# Soprano2G-171.net
KiCad netlist of a schematic drawn in EAGLE
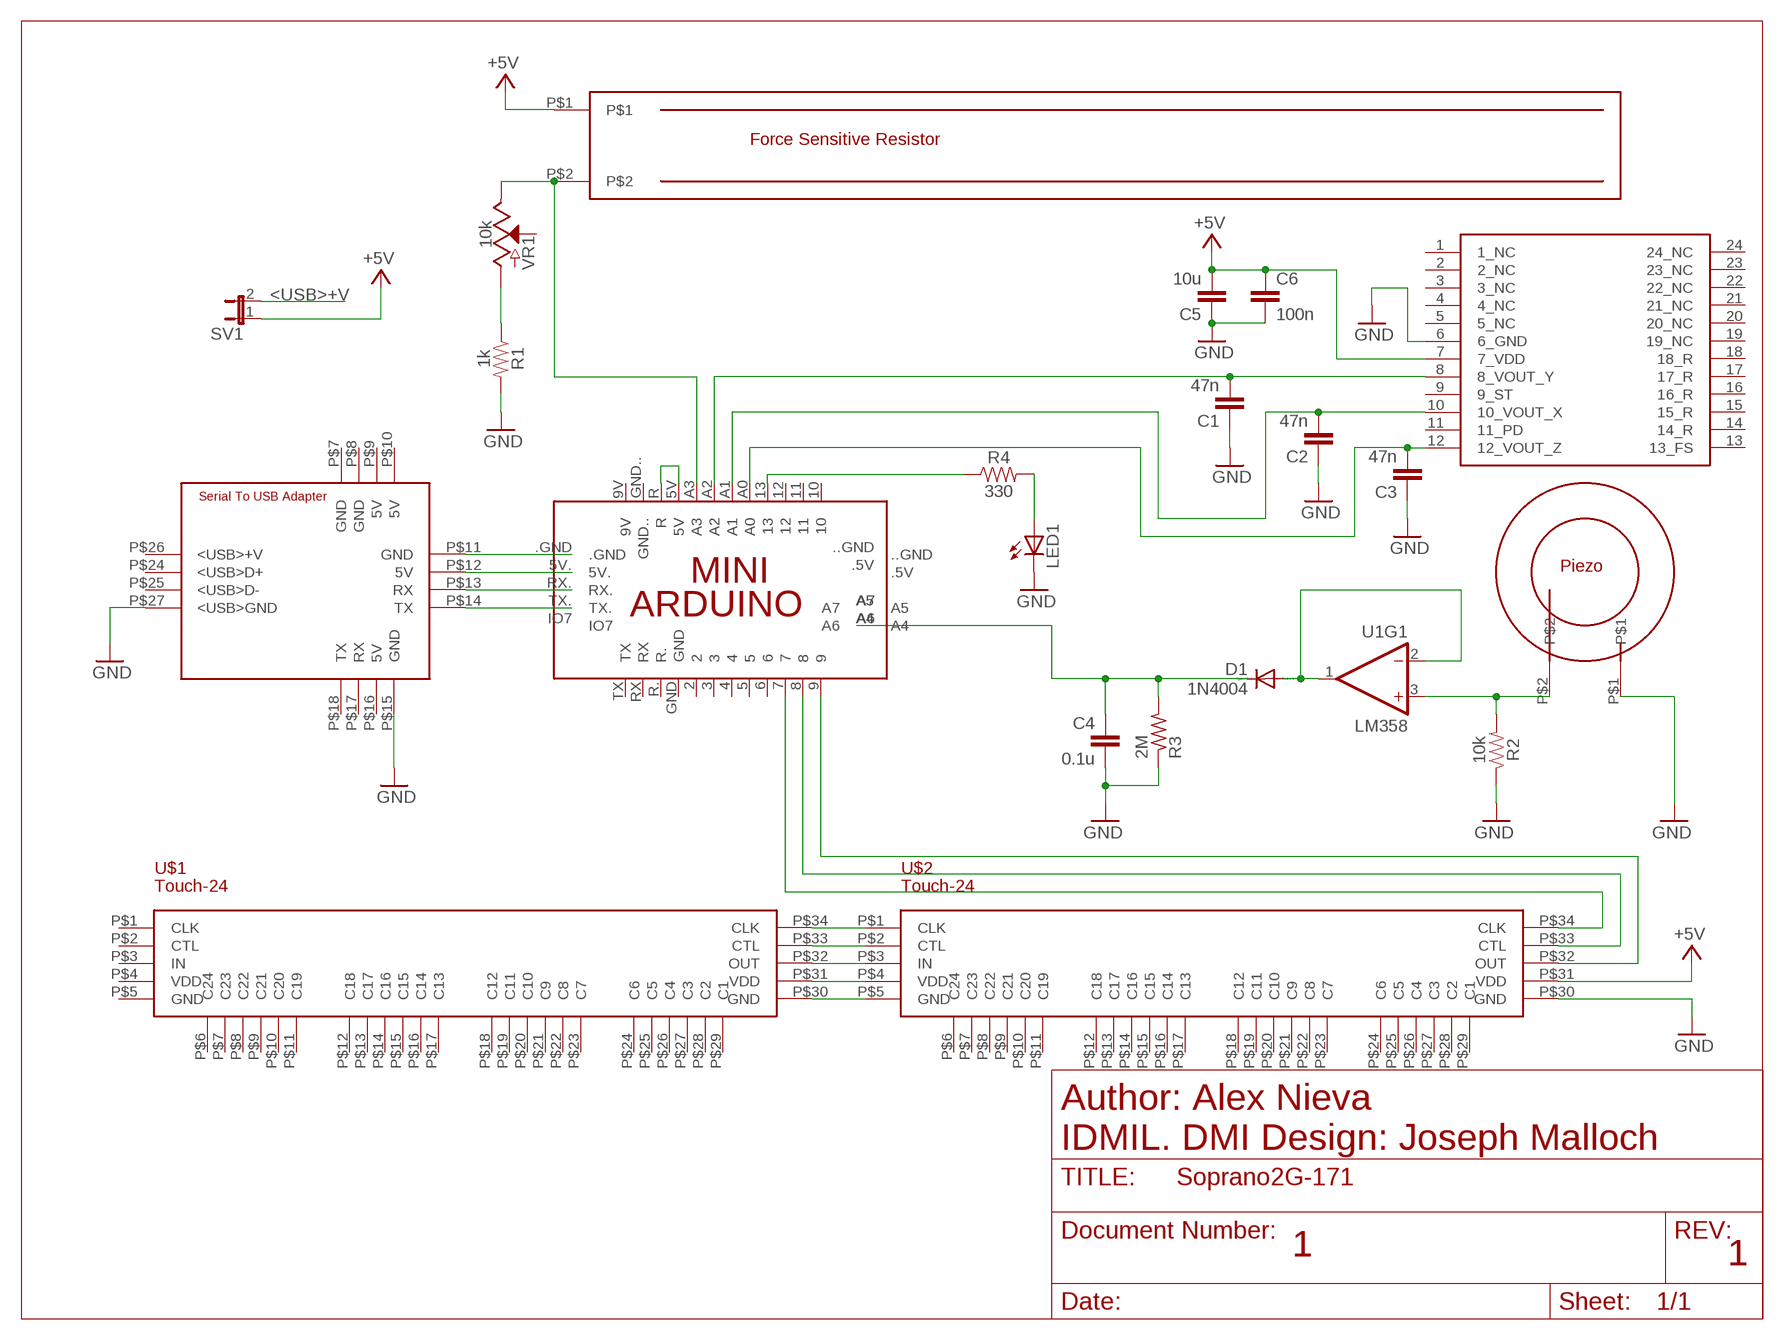
[diagram p0: schematic, sheet 1]

(export (version "E")
  (design (tool "Eeschema 10.0.6"))
  (components
    (comp (ref "C1")
      (value "47n")
      (footprint "eagle-import:C5B5.5")
      (libsource (lib "eagle-import") (part "C5/5.5"))
    )
    (comp (ref "C2")
      (value "47n")
      (footprint "eagle-import:C5B5.5")
      (libsource (lib "eagle-import") (part "C5/5.5"))
    )
    (comp (ref "C3")
      (value "47n")
      (footprint "eagle-import:C5B5.5")
      (libsource (lib "eagle-import") (part "C5/5.5"))
    )
    (comp (ref "C4")
      (value "0.1u")
      (footprint "eagle-import:C5B5.5")
      (libsource (lib "eagle-import") (part "C5/5.5"))
    )
    (comp (ref "C5")
      (value "10u")
      (footprint "eagle-import:C5B5.5")
      (libsource (lib "eagle-import") (part "C5/5.5"))
    )
    (comp (ref "C6")
      (value "100n")
      (footprint "eagle-import:C5B5.5")
      (libsource (lib "eagle-import") (part "C5/5.5"))
    )
    (comp (ref "D1")
      (value "1N4004")
      (footprint "eagle-import:DO41-10")
      (libsource (lib "eagle-import") (part "1N4004"))
    )
    (comp (ref "LED1")
      (value "LED3MM")
      (footprint "eagle-import:LED3MM")
      (libsource (lib "eagle-import") (part "LED3MM"))
    )
    (comp (ref "PCB1")
      (value "ARDUINO_MINI")
      (footprint "eagle-import:ARDUINO_MINI")
      (libsource (lib "eagle-import") (part "ARDUINO_MINI"))
    )
    (comp (ref "R1")
      (value "1k")
      (footprint "eagle-import:AXIAL-0.3")
      (libsource (lib "eagle-import") (part "1KOHM-HORIZ-1/4W-1%"))
    )
    (comp (ref "R2")
      (value "10k")
      (footprint "eagle-import:AXIAL-0.3")
      (libsource (lib "eagle-import") (part "10KOHM-HORIZ-1/4W-1%"))
    )
    (comp (ref "R3")
      (value "2M")
      (footprint "eagle-import:0204_7")
      (libsource (lib "eagle-import") (part "R-US_0204/7"))
    )
    (comp (ref "R4")
      (value "330")
      (footprint "eagle-import:AXIAL-0.3")
      (libsource (lib "eagle-import") (part "1KOHM-HORIZ-1/4W-1%"))
    )
    (comp (ref "SV1")
      (value "JP1E")
      (footprint "eagle-import:JP1")
      (libsource (lib "eagle-import") (part "JP1E"))
    )
    (comp (ref "U$1")
      (value "TOUCH-24TOUCH-24")
      (footprint "eagle-import:TOUCH24")
      (libsource (lib "eagle-import") (part "TOUCH-24TOUCH-24"))
    )
    (comp (ref "U$2")
      (value "TOUCH-24TOUCH-24")
      (footprint "eagle-import:TOUCH24")
      (libsource (lib "eagle-import") (part "TOUCH-24TOUCH-24"))
    )
    (comp (ref "U$3")
      (value "LIS3L02AS4")
      (footprint "eagle-import:SO-24")
      (libsource (lib "eagle-import") (part "LIS3L02AS4"))
    )
    (comp (ref "U$4")
      (value "SERIAL_TO_USB_ARDUINO_MINI")
      (footprint "eagle-import:SERIAL_TO_USB_ARDUINO")
      (libsource (lib "eagle-import") (part "SERIAL_TO_USB_ARDUINO_MINI"))
    )
    (comp (ref "U$5")
      (value "FSR_T-STICK")
      (footprint "eagle-import:FSR_T-STICK")
      (libsource (lib "eagle-import") (part "FSR_T-STICK"))
    )
    (comp (ref "U$6")
      (value "PIEZO_TSTICK")
      (footprint "eagle-import:PIEZO_TSTICK")
      (libsource (lib "eagle-import") (part "PIEZO_TSTICK"))
    )
    (comp (ref "U1")
      (value "LM358")
      (footprint "eagle-import:DIP08")
      (libsource (lib "eagle-import") (part "LM358"))
    )
    (comp (ref "VR1")
      (value "10k")
      (footprint "eagle-import:POT-PTH-ALPS")
      (libsource (lib "eagle-import") (part "POTENTIOMETER-PTH-9MM-1/20W-20%"))
    )
  )
  (nets
    (net (code "1") (name "+5V") (class "Default")
      (node (ref "C5") (pin "2") (pinfunction "2_2") (pintype "passive"))
      (node (ref "C6") (pin "1") (pinfunction "1_1") (pintype "passive"))
      (node (ref "PCB1") (pin "5V.") (pinfunction "5V._5V.") (pintype "bidirectional"))
      (node (ref "SV1") (pin "1") (pinfunction "1_1") (pintype "passive"))
      (node (ref "U$2") (pin "P$31") (pinfunction "VDD_P$31") (pintype "bidirectional"))
      (node (ref "U$3") (pin "7") (pinfunction "7_VDD_7") (pintype "bidirectional"))
      (node (ref "U$4") (pin "P$12") (pinfunction "5V_P$12") (pintype "bidirectional"))
      (node (ref "U$5") (pin "P$1") (pinfunction "P$1_P$1") (pintype "bidirectional"))
    )
    (net (code "2") (name "/<USB>+V") (class "Default")
      (node (ref "SV1") (pin "2") (pinfunction "2_2") (pintype "passive"))
    )
    (net (code "3") (name "GND") (class "Default")
      (node (ref "C1") (pin "1") (pinfunction "1_1") (pintype "passive"))
      (node (ref "C2") (pin "1") (pinfunction "1_1") (pintype "passive"))
      (node (ref "C3") (pin "1") (pinfunction "1_1") (pintype "passive"))
      (node (ref "C4") (pin "2") (pinfunction "2_2") (pintype "passive"))
      (node (ref "C5") (pin "1") (pinfunction "1_1") (pintype "passive"))
      (node (ref "C6") (pin "2") (pinfunction "2_2") (pintype "passive"))
      (node (ref "LED1") (pin "K") (pinfunction "C_K") (pintype "passive"))
      (node (ref "R1") (pin "P$2") (pinfunction "2_P$2") (pintype "passive"))
      (node (ref "R2") (pin "P$1") (pinfunction "1_P$1") (pintype "passive"))
      (node (ref "R3") (pin "1") (pinfunction "1_1") (pintype "passive"))
      (node (ref "U$2") (pin "P$30") (pinfunction "GND_P$30") (pintype "bidirectional"))
      (node (ref "U$3") (pin "6") (pinfunction "6_GND_6") (pintype "bidirectional"))
      (node (ref "U$4") (pin "P$15") (pinfunction "GND_P$15") (pintype "bidirectional"))
      (node (ref "U$4") (pin "P$27") (pinfunction "<USB>GND_P$27") (pintype "bidirectional"))
      (node (ref "U$6") (pin "P$1") (pinfunction "P$1_P$1") (pintype "bidirectional"))
    )
    (net (code "4") (name "Net-(C4-Pad1)") (class "Default")
      (node (ref "C4") (pin "1") (pinfunction "1_1") (pintype "passive"))
      (node (ref "D1") (pin "C") (pinfunction "C_C") (pintype "passive"))
      (node (ref "PCB1") (pin "A6") (pinfunction "A6_A6") (pintype "bidirectional"))
      (node (ref "R3") (pin "2") (pinfunction "2_2") (pintype "passive"))
    )
    (net (code "5") (name "Net-(PCB1-Pad.GND)") (class "Default")
      (node (ref "PCB1") (pin ".GND") (pinfunction ".GND_.GND") (pintype "bidirectional"))
      (node (ref "U$4") (pin "P$11") (pinfunction "GND_P$11") (pintype "bidirectional"))
    )
    (net (code "6") (name "Net-(PCB1-Pad5V)") (class "Default")
      (node (ref "PCB1") (pin "5V") (pinfunction "5V_5V") (pintype "bidirectional"))
      (node (ref "PCB1") (pin "R") (pinfunction "R_R") (pintype "bidirectional"))
    )
    (net (code "7") (name "Net-(PCB1-Pad7)") (class "Default")
      (node (ref "PCB1") (pin "7") (pinfunction "7_7") (pintype "bidirectional"))
      (node (ref "U$2") (pin "P$34") (pinfunction "CLK_P$34") (pintype "bidirectional"))
    )
    (net (code "8") (name "Net-(PCB1-Pad8)") (class "Default")
      (node (ref "PCB1") (pin "8") (pinfunction "8_8") (pintype "bidirectional"))
      (node (ref "U$2") (pin "P$33") (pinfunction "CTL_P$33") (pintype "bidirectional"))
    )
    (net (code "9") (name "Net-(PCB1-PadRX.)") (class "Default")
      (node (ref "PCB1") (pin "RX.") (pinfunction "RX._RX.") (pintype "bidirectional"))
      (node (ref "U$4") (pin "P$13") (pinfunction "RX_P$13") (pintype "bidirectional"))
    )
    (net (code "10") (name "Net-(PCB1-PadTX.)") (class "Default")
      (node (ref "PCB1") (pin "TX.") (pinfunction "TX._TX.") (pintype "bidirectional"))
      (node (ref "U$4") (pin "P$14") (pinfunction "TX_P$14") (pintype "bidirectional"))
    )
    (net (code "11") (name "Net-(R1-1)") (class "Default")
      (node (ref "R1") (pin "P$1") (pinfunction "1_P$1") (pintype "passive"))
      (node (ref "VR1") (pin "P$3") (pinfunction "A_P$3") (pintype "passive"))
    )
    (net (code "12") (name "Net-(R2-2)") (class "Default")
      (node (ref "R2") (pin "P$2") (pinfunction "2_P$2") (pintype "passive"))
      (node (ref "U$6") (pin "P$2") (pinfunction "P$2_P$2") (pintype "bidirectional"))
      (node (ref "U1") (pin "3") (pinfunction "+IN_3") (pintype "input"))
    )
    (net (code "13") (name "Net-(R4-1)") (class "Default")
      (node (ref "PCB1") (pin "13") (pinfunction "13_13") (pintype "bidirectional"))
      (node (ref "R4") (pin "P$1") (pinfunction "1_P$1") (pintype "passive"))
    )
    (net (code "14") (name "Net-(R4-2)") (class "Default")
      (node (ref "LED1") (pin "A") (pinfunction "A_A") (pintype "passive"))
      (node (ref "R4") (pin "P$2") (pinfunction "2_P$2") (pintype "passive"))
    )
    (net (code "15") (name "Net-(U$1-CLK-PadP$34)") (class "Default")
      (node (ref "U$1") (pin "P$34") (pinfunction "CLK_P$34") (pintype "bidirectional"))
      (node (ref "U$2") (pin "P$1") (pinfunction "CLK_P$1") (pintype "bidirectional"))
    )
    (net (code "16") (name "Net-(U$1-CTL-PadP$33)") (class "Default")
      (node (ref "U$1") (pin "P$33") (pinfunction "CTL_P$33") (pintype "bidirectional"))
      (node (ref "U$2") (pin "P$2") (pinfunction "CTL_P$2") (pintype "bidirectional"))
    )
    (net (code "17") (name "Net-(U$1-GND-PadP$30)") (class "Default")
      (node (ref "U$1") (pin "P$30") (pinfunction "GND_P$30") (pintype "bidirectional"))
      (node (ref "U$2") (pin "P$5") (pinfunction "GND_P$5") (pintype "bidirectional"))
    )
    (net (code "18") (name "Net-(U$1-OUT)") (class "Default")
      (node (ref "U$1") (pin "P$32") (pinfunction "OUT_P$32") (pintype "bidirectional"))
      (node (ref "U$2") (pin "P$3") (pinfunction "IN_P$3") (pintype "bidirectional"))
    )
    (net (code "19") (name "Net-(U$1-VDD-PadP$31)") (class "Default")
      (node (ref "U$1") (pin "P$31") (pinfunction "VDD_P$31") (pintype "bidirectional"))
      (node (ref "U$2") (pin "P$4") (pinfunction "VDD_P$4") (pintype "bidirectional"))
    )
    (net (code "20") (name "Net-(U$2-OUT)") (class "Default")
      (node (ref "PCB1") (pin "9") (pinfunction "9_9") (pintype "bidirectional"))
      (node (ref "U$2") (pin "P$32") (pinfunction "OUT_P$32") (pintype "bidirectional"))
    )
    (net (code "21") (name "Net-(U$3-8_VOUT_Y)") (class "Default")
      (node (ref "C1") (pin "2") (pinfunction "2_2") (pintype "passive"))
      (node (ref "PCB1") (pin "A2") (pinfunction "A2_A2") (pintype "bidirectional"))
      (node (ref "U$3") (pin "8") (pinfunction "8_VOUT_Y_8") (pintype "bidirectional"))
    )
    (net (code "22") (name "Net-(U$3-10_VOUT_X)") (class "Default")
      (node (ref "C2") (pin "2") (pinfunction "2_2") (pintype "passive"))
      (node (ref "PCB1") (pin "A1") (pinfunction "A1_A1") (pintype "bidirectional"))
      (node (ref "U$3") (pin "10") (pinfunction "10_VOUT_X_10") (pintype "bidirectional"))
    )
    (net (code "23") (name "Net-(U$3-12_VOUT_Z)") (class "Default")
      (node (ref "C3") (pin "2") (pinfunction "2_2") (pintype "passive"))
      (node (ref "PCB1") (pin "A0") (pinfunction "A0_A0") (pintype "bidirectional"))
      (node (ref "U$3") (pin "12") (pinfunction "12_VOUT_Z_12") (pintype "bidirectional"))
    )
    (net (code "24") (name "Net-(U1A--IN)") (class "Default")
      (node (ref "D1") (pin "A") (pinfunction "A_A") (pintype "passive"))
      (node (ref "U1") (pin "1") (pinfunction "OUT_1") (pintype "output"))
      (node (ref "U1") (pin "2") (pinfunction "-IN_2") (pintype "input"))
    )
    (net (code "25") (name "Net-(VR1-E)") (class "Default")
      (node (ref "PCB1") (pin "A3") (pinfunction "A3_A3") (pintype "bidirectional"))
      (node (ref "U$5") (pin "P$2") (pinfunction "P$2_P$2") (pintype "bidirectional"))
      (node (ref "VR1") (pin "P$1") (pinfunction "E_P$1") (pintype "passive"))
    )
    (net (code "26") (name "unconnected-(PCB1-Pad..GND)") (class "Default")
      (node (ref "PCB1") (pin "..GND") (pinfunction "..GND_..GND") (pintype "bidirectional"))
    )
    (net (code "27") (name "unconnected-(PCB1-Pad.5V)") (class "Default")
      (node (ref "PCB1") (pin ".5V") (pinfunction ".5V_.5V") (pintype "bidirectional"))
    )
    (net (code "28") (name "unconnected-(PCB1-Pad2)") (class "Default")
      (node (ref "PCB1") (pin "2") (pinfunction "2_2") (pintype "bidirectional"))
    )
    (net (code "29") (name "unconnected-(PCB1-Pad3)") (class "Default")
      (node (ref "PCB1") (pin "3") (pinfunction "3_3") (pintype "bidirectional"))
    )
    (net (code "30") (name "unconnected-(PCB1-Pad4)") (class "Default")
      (node (ref "PCB1") (pin "4") (pinfunction "4_4") (pintype "bidirectional"))
    )
    (net (code "31") (name "unconnected-(PCB1-Pad5)") (class "Default")
      (node (ref "PCB1") (pin "5") (pinfunction "5_5") (pintype "bidirectional"))
    )
    (net (code "32") (name "unconnected-(PCB1-Pad6)") (class "Default")
      (node (ref "PCB1") (pin "6") (pinfunction "6_6") (pintype "bidirectional"))
    )
    (net (code "33") (name "unconnected-(PCB1-Pad9V)") (class "Default")
      (node (ref "PCB1") (pin "9V") (pinfunction "9V_9V") (pintype "bidirectional"))
    )
    (net (code "34") (name "unconnected-(PCB1-Pad10)") (class "Default")
      (node (ref "PCB1") (pin "10") (pinfunction "10_10") (pintype "bidirectional"))
    )
    (net (code "35") (name "unconnected-(PCB1-Pad11)") (class "Default")
      (node (ref "PCB1") (pin "11") (pinfunction "11_11") (pintype "bidirectional"))
    )
    (net (code "36") (name "unconnected-(PCB1-Pad12)") (class "Default")
      (node (ref "PCB1") (pin "12") (pinfunction "12_12") (pintype "bidirectional"))
    )
    (net (code "37") (name "unconnected-(PCB1-PadA4)") (class "Default")
      (node (ref "PCB1") (pin "A4") (pinfunction "A4_A4") (pintype "bidirectional"))
    )
    (net (code "38") (name "unconnected-(PCB1-PadA5)") (class "Default")
      (node (ref "PCB1") (pin "A5") (pinfunction "A5_A5") (pintype "bidirectional"))
    )
    (net (code "39") (name "unconnected-(PCB1-PadA7)") (class "Default")
      (node (ref "PCB1") (pin "A7") (pinfunction "A7_A7") (pintype "bidirectional"))
    )
    (net (code "40") (name "unconnected-(PCB1-PadGND)") (class "Default")
      (node (ref "PCB1") (pin "GND") (pinfunction "GND_GND") (pintype "bidirectional"))
    )
    (net (code "41") (name "unconnected-(PCB1-PadGND..)") (class "Default")
      (node (ref "PCB1") (pin "GND..") (pinfunction "GND.._GND..") (pintype "bidirectional"))
    )
    (net (code "42") (name "unconnected-(PCB1-PadIO7)") (class "Default")
      (node (ref "PCB1") (pin "IO7") (pinfunction "IO7_IO7") (pintype "bidirectional"))
    )
    (net (code "43") (name "unconnected-(PCB1-PadR.)") (class "Default")
      (node (ref "PCB1") (pin "R.") (pinfunction "R._R.") (pintype "bidirectional"))
    )
    (net (code "44") (name "unconnected-(PCB1-PadRX)") (class "Default")
      (node (ref "PCB1") (pin "RX") (pinfunction "RX_RX") (pintype "bidirectional"))
    )
    (net (code "45") (name "unconnected-(PCB1-PadTX)") (class "Default")
      (node (ref "PCB1") (pin "TX") (pinfunction "TX_TX") (pintype "bidirectional"))
    )
    (net (code "46") (name "unconnected-(U$1-C1-PadP$29)") (class "Default")
      (node (ref "U$1") (pin "P$29") (pinfunction "C1_P$29") (pintype "bidirectional"))
    )
    (net (code "47") (name "unconnected-(U$1-C2-PadP$28)") (class "Default")
      (node (ref "U$1") (pin "P$28") (pinfunction "C2_P$28") (pintype "bidirectional"))
    )
    (net (code "48") (name "unconnected-(U$1-C3-PadP$27)") (class "Default")
      (node (ref "U$1") (pin "P$27") (pinfunction "C3_P$27") (pintype "bidirectional"))
    )
    (net (code "49") (name "unconnected-(U$1-C4-PadP$26)") (class "Default")
      (node (ref "U$1") (pin "P$26") (pinfunction "C4_P$26") (pintype "bidirectional"))
    )
    (net (code "50") (name "unconnected-(U$1-C5-PadP$25)") (class "Default")
      (node (ref "U$1") (pin "P$25") (pinfunction "C5_P$25") (pintype "bidirectional"))
    )
    (net (code "51") (name "unconnected-(U$1-C6-PadP$24)") (class "Default")
      (node (ref "U$1") (pin "P$24") (pinfunction "C6_P$24") (pintype "bidirectional"))
    )
    (net (code "52") (name "unconnected-(U$1-C7-PadP$23)") (class "Default")
      (node (ref "U$1") (pin "P$23") (pinfunction "C7_P$23") (pintype "bidirectional"))
    )
    (net (code "53") (name "unconnected-(U$1-C8-PadP$22)") (class "Default")
      (node (ref "U$1") (pin "P$22") (pinfunction "C8_P$22") (pintype "bidirectional"))
    )
    (net (code "54") (name "unconnected-(U$1-C9-PadP$21)") (class "Default")
      (node (ref "U$1") (pin "P$21") (pinfunction "C9_P$21") (pintype "bidirectional"))
    )
    (net (code "55") (name "unconnected-(U$1-C10-PadP$20)") (class "Default")
      (node (ref "U$1") (pin "P$20") (pinfunction "C10_P$20") (pintype "bidirectional"))
    )
    (net (code "56") (name "unconnected-(U$1-C11-PadP$19)") (class "Default")
      (node (ref "U$1") (pin "P$19") (pinfunction "C11_P$19") (pintype "bidirectional"))
    )
    (net (code "57") (name "unconnected-(U$1-C12-PadP$18)") (class "Default")
      (node (ref "U$1") (pin "P$18") (pinfunction "C12_P$18") (pintype "bidirectional"))
    )
    (net (code "58") (name "unconnected-(U$1-C13-PadP$17)") (class "Default")
      (node (ref "U$1") (pin "P$17") (pinfunction "C13_P$17") (pintype "bidirectional"))
    )
    (net (code "59") (name "unconnected-(U$1-C14-PadP$16)") (class "Default")
      (node (ref "U$1") (pin "P$16") (pinfunction "C14_P$16") (pintype "bidirectional"))
    )
    (net (code "60") (name "unconnected-(U$1-C15-PadP$15)") (class "Default")
      (node (ref "U$1") (pin "P$15") (pinfunction "C15_P$15") (pintype "bidirectional"))
    )
    (net (code "61") (name "unconnected-(U$1-C16-PadP$14)") (class "Default")
      (node (ref "U$1") (pin "P$14") (pinfunction "C16_P$14") (pintype "bidirectional"))
    )
    (net (code "62") (name "unconnected-(U$1-C17-PadP$13)") (class "Default")
      (node (ref "U$1") (pin "P$13") (pinfunction "C17_P$13") (pintype "bidirectional"))
    )
    (net (code "63") (name "unconnected-(U$1-C18-PadP$12)") (class "Default")
      (node (ref "U$1") (pin "P$12") (pinfunction "C18_P$12") (pintype "bidirectional"))
    )
    (net (code "64") (name "unconnected-(U$1-C19-PadP$11)") (class "Default")
      (node (ref "U$1") (pin "P$11") (pinfunction "C19_P$11") (pintype "bidirectional"))
    )
    (net (code "65") (name "unconnected-(U$1-C20-PadP$10)") (class "Default")
      (node (ref "U$1") (pin "P$10") (pinfunction "C20_P$10") (pintype "bidirectional"))
    )
    (net (code "66") (name "unconnected-(U$1-C21-PadP$9)") (class "Default")
      (node (ref "U$1") (pin "P$9") (pinfunction "C21_P$9") (pintype "bidirectional"))
    )
    (net (code "67") (name "unconnected-(U$1-C22-PadP$8)") (class "Default")
      (node (ref "U$1") (pin "P$8") (pinfunction "C22_P$8") (pintype "bidirectional"))
    )
    (net (code "68") (name "unconnected-(U$1-C23-PadP$7)") (class "Default")
      (node (ref "U$1") (pin "P$7") (pinfunction "C23_P$7") (pintype "bidirectional"))
    )
    (net (code "69") (name "unconnected-(U$1-C24-PadP$6)") (class "Default")
      (node (ref "U$1") (pin "P$6") (pinfunction "C24_P$6") (pintype "bidirectional"))
    )
    (net (code "70") (name "unconnected-(U$1-CLK-PadP$1)") (class "Default")
      (node (ref "U$1") (pin "P$1") (pinfunction "CLK_P$1") (pintype "bidirectional"))
    )
    (net (code "71") (name "unconnected-(U$1-CTL-PadP$2)") (class "Default")
      (node (ref "U$1") (pin "P$2") (pinfunction "CTL_P$2") (pintype "bidirectional"))
    )
    (net (code "72") (name "unconnected-(U$1-GND-PadP$5)") (class "Default")
      (node (ref "U$1") (pin "P$5") (pinfunction "GND_P$5") (pintype "bidirectional"))
    )
    (net (code "73") (name "unconnected-(U$1-IN-PadP$3)") (class "Default")
      (node (ref "U$1") (pin "P$3") (pinfunction "IN_P$3") (pintype "bidirectional"))
    )
    (net (code "74") (name "unconnected-(U$1-VDD-PadP$4)") (class "Default")
      (node (ref "U$1") (pin "P$4") (pinfunction "VDD_P$4") (pintype "bidirectional"))
    )
    (net (code "75") (name "unconnected-(U$2-C1-PadP$29)") (class "Default")
      (node (ref "U$2") (pin "P$29") (pinfunction "C1_P$29") (pintype "bidirectional"))
    )
    (net (code "76") (name "unconnected-(U$2-C2-PadP$28)") (class "Default")
      (node (ref "U$2") (pin "P$28") (pinfunction "C2_P$28") (pintype "bidirectional"))
    )
    (net (code "77") (name "unconnected-(U$2-C3-PadP$27)") (class "Default")
      (node (ref "U$2") (pin "P$27") (pinfunction "C3_P$27") (pintype "bidirectional"))
    )
    (net (code "78") (name "unconnected-(U$2-C4-PadP$26)") (class "Default")
      (node (ref "U$2") (pin "P$26") (pinfunction "C4_P$26") (pintype "bidirectional"))
    )
    (net (code "79") (name "unconnected-(U$2-C5-PadP$25)") (class "Default")
      (node (ref "U$2") (pin "P$25") (pinfunction "C5_P$25") (pintype "bidirectional"))
    )
    (net (code "80") (name "unconnected-(U$2-C6-PadP$24)") (class "Default")
      (node (ref "U$2") (pin "P$24") (pinfunction "C6_P$24") (pintype "bidirectional"))
    )
    (net (code "81") (name "unconnected-(U$2-C7-PadP$23)") (class "Default")
      (node (ref "U$2") (pin "P$23") (pinfunction "C7_P$23") (pintype "bidirectional"))
    )
    (net (code "82") (name "unconnected-(U$2-C8-PadP$22)") (class "Default")
      (node (ref "U$2") (pin "P$22") (pinfunction "C8_P$22") (pintype "bidirectional"))
    )
    (net (code "83") (name "unconnected-(U$2-C9-PadP$21)") (class "Default")
      (node (ref "U$2") (pin "P$21") (pinfunction "C9_P$21") (pintype "bidirectional"))
    )
    (net (code "84") (name "unconnected-(U$2-C10-PadP$20)") (class "Default")
      (node (ref "U$2") (pin "P$20") (pinfunction "C10_P$20") (pintype "bidirectional"))
    )
    (net (code "85") (name "unconnected-(U$2-C11-PadP$19)") (class "Default")
      (node (ref "U$2") (pin "P$19") (pinfunction "C11_P$19") (pintype "bidirectional"))
    )
    (net (code "86") (name "unconnected-(U$2-C12-PadP$18)") (class "Default")
      (node (ref "U$2") (pin "P$18") (pinfunction "C12_P$18") (pintype "bidirectional"))
    )
    (net (code "87") (name "unconnected-(U$2-C13-PadP$17)") (class "Default")
      (node (ref "U$2") (pin "P$17") (pinfunction "C13_P$17") (pintype "bidirectional"))
    )
    (net (code "88") (name "unconnected-(U$2-C14-PadP$16)") (class "Default")
      (node (ref "U$2") (pin "P$16") (pinfunction "C14_P$16") (pintype "bidirectional"))
    )
    (net (code "89") (name "unconnected-(U$2-C15-PadP$15)") (class "Default")
      (node (ref "U$2") (pin "P$15") (pinfunction "C15_P$15") (pintype "bidirectional"))
    )
    (net (code "90") (name "unconnected-(U$2-C16-PadP$14)") (class "Default")
      (node (ref "U$2") (pin "P$14") (pinfunction "C16_P$14") (pintype "bidirectional"))
    )
    (net (code "91") (name "unconnected-(U$2-C17-PadP$13)") (class "Default")
      (node (ref "U$2") (pin "P$13") (pinfunction "C17_P$13") (pintype "bidirectional"))
    )
    (net (code "92") (name "unconnected-(U$2-C18-PadP$12)") (class "Default")
      (node (ref "U$2") (pin "P$12") (pinfunction "C18_P$12") (pintype "bidirectional"))
    )
    (net (code "93") (name "unconnected-(U$2-C19-PadP$11)") (class "Default")
      (node (ref "U$2") (pin "P$11") (pinfunction "C19_P$11") (pintype "bidirectional"))
    )
    (net (code "94") (name "unconnected-(U$2-C20-PadP$10)") (class "Default")
      (node (ref "U$2") (pin "P$10") (pinfunction "C20_P$10") (pintype "bidirectional"))
    )
    (net (code "95") (name "unconnected-(U$2-C21-PadP$9)") (class "Default")
      (node (ref "U$2") (pin "P$9") (pinfunction "C21_P$9") (pintype "bidirectional"))
    )
    (net (code "96") (name "unconnected-(U$2-C22-PadP$8)") (class "Default")
      (node (ref "U$2") (pin "P$8") (pinfunction "C22_P$8") (pintype "bidirectional"))
    )
    (net (code "97") (name "unconnected-(U$2-C23-PadP$7)") (class "Default")
      (node (ref "U$2") (pin "P$7") (pinfunction "C23_P$7") (pintype "bidirectional"))
    )
    (net (code "98") (name "unconnected-(U$2-C24-PadP$6)") (class "Default")
      (node (ref "U$2") (pin "P$6") (pinfunction "C24_P$6") (pintype "bidirectional"))
    )
    (net (code "99") (name "unconnected-(U$3-1_NC-Pad1)") (class "Default")
      (node (ref "U$3") (pin "1") (pinfunction "1_NC_1") (pintype "bidirectional"))
    )
    (net (code "100") (name "unconnected-(U$3-2_NC-Pad2)") (class "Default")
      (node (ref "U$3") (pin "2") (pinfunction "2_NC_2") (pintype "bidirectional"))
    )
    (net (code "101") (name "unconnected-(U$3-3_NC-Pad3)") (class "Default")
      (node (ref "U$3") (pin "3") (pinfunction "3_NC_3") (pintype "bidirectional"))
    )
    (net (code "102") (name "unconnected-(U$3-4_NC-Pad4)") (class "Default")
      (node (ref "U$3") (pin "4") (pinfunction "4_NC_4") (pintype "bidirectional"))
    )
    (net (code "103") (name "unconnected-(U$3-5_NC-Pad5)") (class "Default")
      (node (ref "U$3") (pin "5") (pinfunction "5_NC_5") (pintype "bidirectional"))
    )
    (net (code "104") (name "unconnected-(U$3-9_ST-Pad9)") (class "Default")
      (node (ref "U$3") (pin "9") (pinfunction "9_ST_9") (pintype "bidirectional"))
    )
    (net (code "105") (name "unconnected-(U$3-11_PD-Pad11)") (class "Default")
      (node (ref "U$3") (pin "11") (pinfunction "11_PD_11") (pintype "bidirectional"))
    )
    (net (code "106") (name "unconnected-(U$3-13_FS-Pad13)") (class "Default")
      (node (ref "U$3") (pin "13") (pinfunction "13_FS_13") (pintype "bidirectional"))
    )
    (net (code "107") (name "unconnected-(U$3-14_R-Pad14)") (class "Default")
      (node (ref "U$3") (pin "14") (pinfunction "14_R_14") (pintype "bidirectional"))
    )
    (net (code "108") (name "unconnected-(U$3-15_R-Pad15)") (class "Default")
      (node (ref "U$3") (pin "15") (pinfunction "15_R_15") (pintype "bidirectional"))
    )
    (net (code "109") (name "unconnected-(U$3-16_R-Pad16)") (class "Default")
      (node (ref "U$3") (pin "16") (pinfunction "16_R_16") (pintype "bidirectional"))
    )
    (net (code "110") (name "unconnected-(U$3-17_R-Pad17)") (class "Default")
      (node (ref "U$3") (pin "17") (pinfunction "17_R_17") (pintype "bidirectional"))
    )
    (net (code "111") (name "unconnected-(U$3-18_R-Pad18)") (class "Default")
      (node (ref "U$3") (pin "18") (pinfunction "18_R_18") (pintype "bidirectional"))
    )
    (net (code "112") (name "unconnected-(U$3-19_NC-Pad19)") (class "Default")
      (node (ref "U$3") (pin "19") (pinfunction "19_NC_19") (pintype "bidirectional"))
    )
    (net (code "113") (name "unconnected-(U$3-20_NC-Pad20)") (class "Default")
      (node (ref "U$3") (pin "20") (pinfunction "20_NC_20") (pintype "bidirectional"))
    )
    (net (code "114") (name "unconnected-(U$3-21_NC-Pad21)") (class "Default")
      (node (ref "U$3") (pin "21") (pinfunction "21_NC_21") (pintype "bidirectional"))
    )
    (net (code "115") (name "unconnected-(U$3-22_NC-Pad22)") (class "Default")
      (node (ref "U$3") (pin "22") (pinfunction "22_NC_22") (pintype "bidirectional"))
    )
    (net (code "116") (name "unconnected-(U$3-23_NC-Pad23)") (class "Default")
      (node (ref "U$3") (pin "23") (pinfunction "23_NC_23") (pintype "bidirectional"))
    )
    (net (code "117") (name "unconnected-(U$3-24_NC-Pad24)") (class "Default")
      (node (ref "U$3") (pin "24") (pinfunction "24_NC_24") (pintype "bidirectional"))
    )
    (net (code "118") (name "unconnected-(U$4-5V-PadP$9)") (class "Default")
      (node (ref "U$4") (pin "P$9") (pinfunction "5V_P$9") (pintype "bidirectional"))
    )
    (net (code "119") (name "unconnected-(U$4-5V-PadP$10)") (class "Default")
      (node (ref "U$4") (pin "P$10") (pinfunction "5V_P$10") (pintype "bidirectional"))
    )
    (net (code "120") (name "unconnected-(U$4-5V-PadP$16)") (class "Default")
      (node (ref "U$4") (pin "P$16") (pinfunction "5V_P$16") (pintype "bidirectional"))
    )
    (net (code "121") (name "unconnected-(U$4-<USB>+V-PadP$26)") (class "Default")
      (node (ref "U$4") (pin "P$26") (pinfunction "<USB>+V_P$26") (pintype "bidirectional"))
    )
    (net (code "122") (name "unconnected-(U$4-<USB>D+-PadP$24)") (class "Default")
      (node (ref "U$4") (pin "P$24") (pinfunction "<USB>D+_P$24") (pintype "bidirectional"))
    )
    (net (code "123") (name "unconnected-(U$4-<USB>D--PadP$25)") (class "Default")
      (node (ref "U$4") (pin "P$25") (pinfunction "<USB>D-_P$25") (pintype "bidirectional"))
    )
    (net (code "124") (name "unconnected-(U$4-GND-PadP$7)") (class "Default")
      (node (ref "U$4") (pin "P$7") (pinfunction "GND_P$7") (pintype "bidirectional"))
    )
    (net (code "125") (name "unconnected-(U$4-GND-PadP$8)") (class "Default")
      (node (ref "U$4") (pin "P$8") (pinfunction "GND_P$8") (pintype "bidirectional"))
    )
    (net (code "126") (name "unconnected-(U$4-RX-PadP$17)") (class "Default")
      (node (ref "U$4") (pin "P$17") (pinfunction "RX_P$17") (pintype "bidirectional"))
    )
    (net (code "127") (name "unconnected-(U$4-TX-PadP$18)") (class "Default")
      (node (ref "U$4") (pin "P$18") (pinfunction "TX_P$18") (pintype "bidirectional"))
    )
    (net (code "128") (name "unconnected-(VR1-S-PadP$2)") (class "Default")
      (node (ref "VR1") (pin "P$2") (pinfunction "S_P$2") (pintype "passive"))
    )
  )
)
